# ManniRaspiRadio.net
KiCad netlist of a schematic drawn in EAGLE
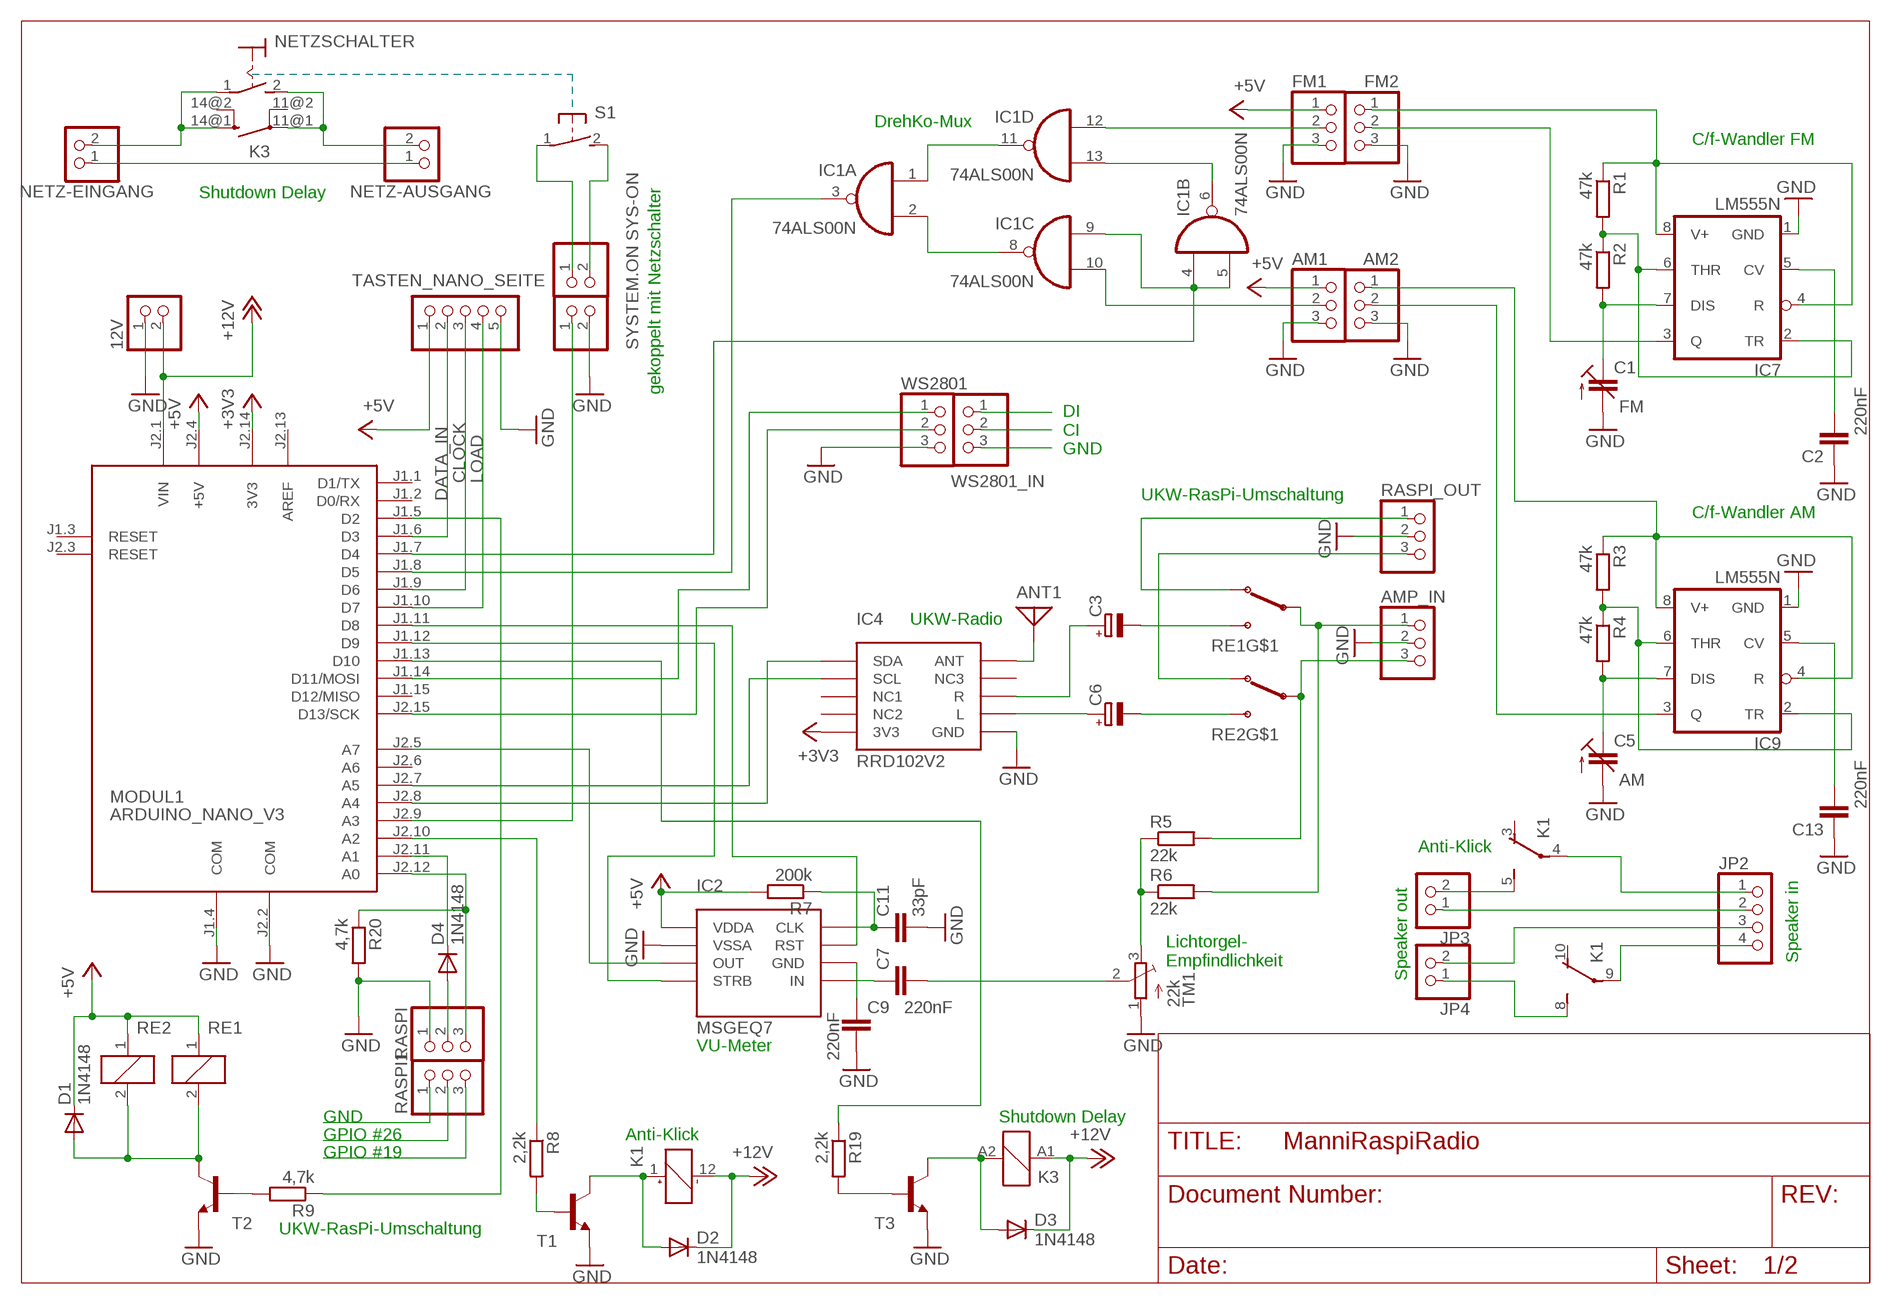
[diagram p0: schematic, sheet 1]
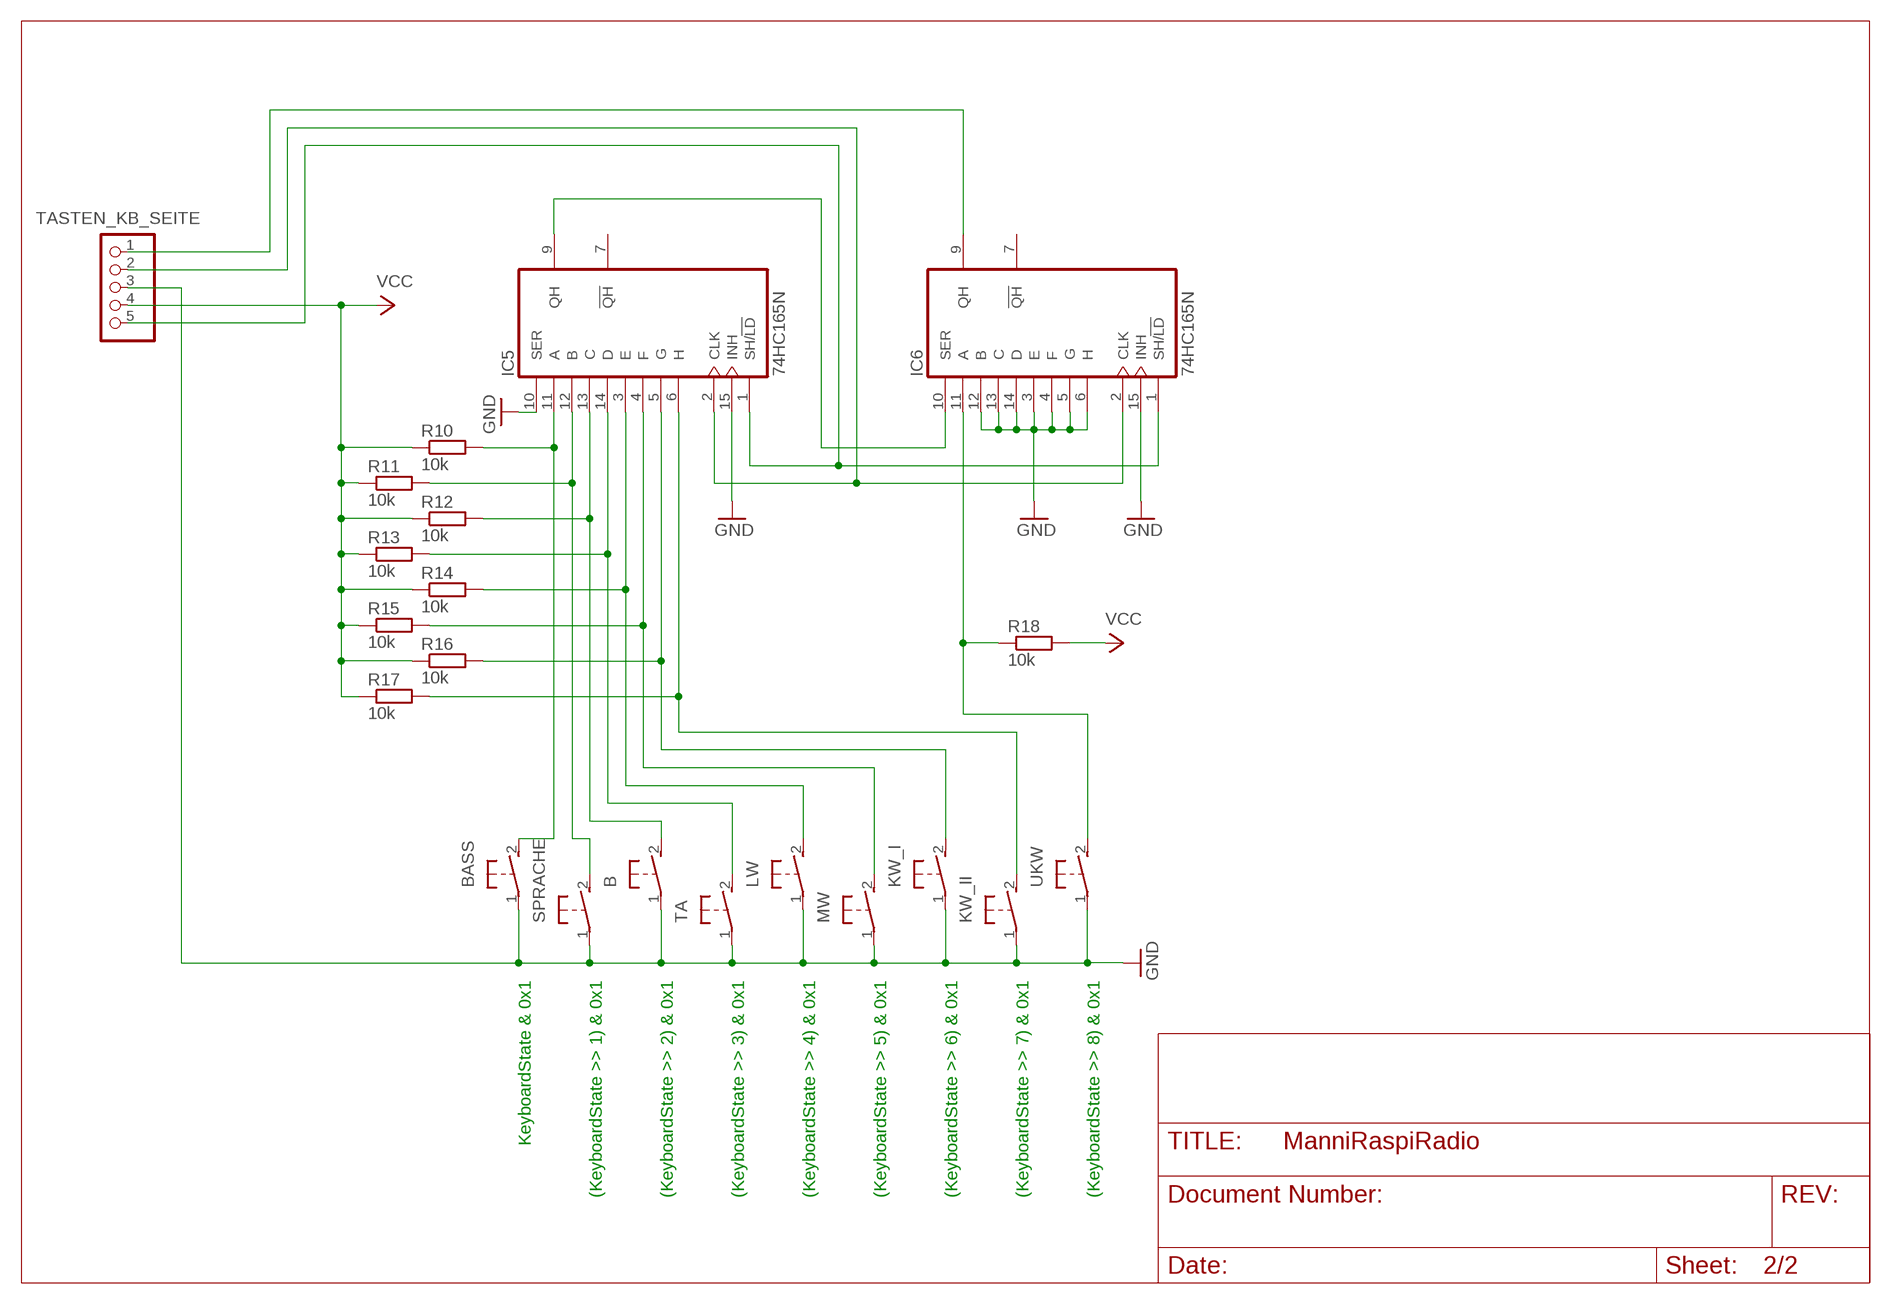
[diagram p1: schematic, sheet 2]

(export (version "E")
  (design (tool "Eeschema 10.0.6"))
  (components
    (comp (ref "12V")
      (value "PINHD-1X2")
      (footprint "eagle-import:1X02")
      (libsource (lib "eagle-import") (part "PINHD-1X2"))
    )
    (comp (ref "AM1")
      (value "PINHD-1X3")
      (footprint "eagle-import:1X03")
      (libsource (lib "eagle-import") (part "PINHD-1X3"))
    )
    (comp (ref "AM2")
      (value "PINHD-1X3")
      (footprint "eagle-import:1X03")
      (libsource (lib "eagle-import") (part "PINHD-1X3"))
    )
    (comp (ref "AMP_IN")
      (value "PINHD-1X3")
      (footprint "eagle-import:1X03")
      (libsource (lib "eagle-import") (part "PINHD-1X3"))
    )
    (comp (ref "ANT1")
      (value "ANTENNA")
      (footprint "eagle-import:PAD-01")
      (libsource (lib "eagle-import") (part "ANTENNA"))
    )
    (comp (ref "C1")
      (value "FM")
      (footprint "eagle-import:CTRIM3018_12")
      (libsource (lib "eagle-import") (part "C-TRIMM3018_12"))
    )
    (comp (ref "C2")
      (value "220nF")
      (footprint "eagle-import:C025-030X050")
      (libsource (lib "eagle-import") (part "C-EU025-030X050"))
    )
    (comp (ref "C3")
      (value "CPOL-EU139CLL-2W")
      (footprint "eagle-import:139CLL-2W")
      (libsource (lib "eagle-import") (part "CPOL-EU139CLL-2W"))
    )
    (comp (ref "C5")
      (value "AM")
      (footprint "eagle-import:CTRIM3018_12")
      (libsource (lib "eagle-import") (part "C-TRIMM3018_12"))
    )
    (comp (ref "C6")
      (value "CPOL-EU139CLL-2W")
      (footprint "eagle-import:139CLL-2W")
      (libsource (lib "eagle-import") (part "CPOL-EU139CLL-2W"))
    )
    (comp (ref "C7")
      (value "220nF")
      (footprint "eagle-import:C025-030X050")
      (libsource (lib "eagle-import") (part "C-EU025-030X050"))
    )
    (comp (ref "C9")
      (value "220nF")
      (footprint "eagle-import:C025-030X050")
      (libsource (lib "eagle-import") (part "C-EU025-030X050"))
    )
    (comp (ref "C11")
      (value "33pF")
      (footprint "eagle-import:C025-030X050")
      (libsource (lib "eagle-import") (part "C-EU025-030X050"))
    )
    (comp (ref "C13")
      (value "220nF")
      (footprint "eagle-import:C025-030X050")
      (libsource (lib "eagle-import") (part "C-EU025-030X050"))
    )
    (comp (ref "D1")
      (value "1N4148")
      (footprint "eagle-import:DO35-10")
      (libsource (lib "eagle-import") (part "1N4148DO35-10"))
    )
    (comp (ref "D2")
      (value "1N4148")
      (footprint "eagle-import:DO35-10")
      (libsource (lib "eagle-import") (part "1N4148DO35-10"))
    )
    (comp (ref "D3")
      (value "1N4148")
      (footprint "eagle-import:DO35-10")
      (libsource (lib "eagle-import") (part "1N4148DO35-10"))
    )
    (comp (ref "D4")
      (value "1N4148")
      (footprint "eagle-import:DO35-10")
      (libsource (lib "eagle-import") (part "1N4148DO35-10"))
    )
    (comp (ref "FM1")
      (value "PINHD-1X3")
      (footprint "eagle-import:1X03")
      (libsource (lib "eagle-import") (part "PINHD-1X3"))
    )
    (comp (ref "FM2")
      (value "PINHD-1X3")
      (footprint "eagle-import:1X03")
      (libsource (lib "eagle-import") (part "PINHD-1X3"))
    )
    (comp (ref "IC1")
      (value "74ALS00N")
      (footprint "eagle-import:DIL14")
      (libsource (lib "eagle-import") (part "7400NALS"))
    )
    (comp (ref "IC2")
      (value "MSGEQ7")
      (footprint "eagle-import:MSGEQ7")
      (libsource (lib "eagle-import") (part "MSGEQ7"))
    )
    (comp (ref "IC4")
      (value "RRD102V2")
      (footprint "eagle-import:RRD102V2")
      (libsource (lib "eagle-import") (part "RRD102V2"))
    )
    (comp (ref "IC7")
      (value "LM555N")
      (footprint "eagle-import:DIL08")
      (libsource (lib "eagle-import") (part "555NLM"))
    )
    (comp (ref "IC9")
      (value "LM555N")
      (footprint "eagle-import:DIL08")
      (libsource (lib "eagle-import") (part "555NLM"))
    )
    (comp (ref "JP2")
      (value "PINHD-1X4")
      (footprint "eagle-import:1X04")
      (libsource (lib "eagle-import") (part "PINHD-1X4"))
    )
    (comp (ref "JP3")
      (value "PINHD-1X2")
      (footprint "eagle-import:1X02")
      (libsource (lib "eagle-import") (part "PINHD-1X2"))
    )
    (comp (ref "JP4")
      (value "PINHD-1X2")
      (footprint "eagle-import:1X02")
      (libsource (lib "eagle-import") (part "PINHD-1X2"))
    )
    (comp (ref "K1")
      (value "TXD2-12V")
      (footprint "eagle-import:TXD2")
      (libsource (lib "eagle-import") (part "TX?-D212V"))
    )
    (comp (ref "K3")
      (value "FINDER-43.61")
      (footprint "eagle-import:FINDER-43.61")
      (libsource (lib "eagle-import") (part "FINDER-43.61"))
    )
    (comp (ref "MODUL1")
      (value "ARDUINO_NANO_V3")
      (footprint "eagle-import:ARDUINO_NANO2")
      (libsource (lib "eagle-import") (part "ARDUINO_NANO2"))
    )
    (comp (ref "NETZ-AUSGANG")
      (value "PINHD-1X2")
      (footprint "eagle-import:1X02")
      (libsource (lib "eagle-import") (part "PINHD-1X2"))
    )
    (comp (ref "NETZ-EINGANG")
      (value "PINHD-1X2")
      (footprint "eagle-import:1X02")
      (libsource (lib "eagle-import") (part "PINHD-1X2"))
    )
    (comp (ref "NETZSCHALTER")
      (value "MS243")
      (footprint "eagle-import:MS243")
      (libsource (lib "eagle-import") (part "MS243"))
    )
    (comp (ref "R1")
      (value "47k")
      (footprint "eagle-import:0207_10")
      (libsource (lib "eagle-import") (part "R-EU_0207/10"))
    )
    (comp (ref "R2")
      (value "47k")
      (footprint "eagle-import:0207_10")
      (libsource (lib "eagle-import") (part "R-EU_0207/10"))
    )
    (comp (ref "R3")
      (value "47k")
      (footprint "eagle-import:0207_10")
      (libsource (lib "eagle-import") (part "R-EU_0207/10"))
    )
    (comp (ref "R4")
      (value "47k")
      (footprint "eagle-import:0207_10")
      (libsource (lib "eagle-import") (part "R-EU_0207/10"))
    )
    (comp (ref "R5")
      (value "22k")
      (footprint "eagle-import:0207_10")
      (libsource (lib "eagle-import") (part "R-EU_0207/10"))
    )
    (comp (ref "R6")
      (value "22k")
      (footprint "eagle-import:0207_10")
      (libsource (lib "eagle-import") (part "R-EU_0207/10"))
    )
    (comp (ref "R7")
      (value "200k")
      (footprint "eagle-import:0207_10")
      (libsource (lib "eagle-import") (part "R-EU_0207/10"))
    )
    (comp (ref "R8")
      (value "2,2k")
      (footprint "eagle-import:0207_10")
      (libsource (lib "eagle-import") (part "R-EU_0207/10"))
    )
    (comp (ref "R9")
      (value "4,7k")
      (footprint "eagle-import:0207_10")
      (libsource (lib "eagle-import") (part "R-EU_0207/10"))
    )
    (comp (ref "R19")
      (value "2,2k")
      (footprint "eagle-import:0207_10")
      (libsource (lib "eagle-import") (part "R-EU_0207/10"))
    )
    (comp (ref "R20")
      (value "4,7k")
      (footprint "eagle-import:0207_10")
      (libsource (lib "eagle-import") (part "R-EU_0207/10"))
    )
    (comp (ref "RASPI")
      (value "PINHD-1X3")
      (footprint "eagle-import:1X03")
      (libsource (lib "eagle-import") (part "PINHD-1X3"))
    )
    (comp (ref "RASPI1")
      (value "PINHD-1X3")
      (footprint "eagle-import:1X03")
      (libsource (lib "eagle-import") (part "PINHD-1X3"))
    )
    (comp (ref "RASPI_OUT")
      (value "PINHD-1X3")
      (footprint "eagle-import:1X03")
      (libsource (lib "eagle-import") (part "PINHD-1X3"))
    )
    (comp (ref "RE1")
      (value "RE-SPDT--G5LE")
      (footprint "eagle-import:EPP-RELAY-G5LE")
      (libsource (lib "eagle-import") (part "RE-SPDT--G5LE"))
    )
    (comp (ref "RE2")
      (value "RE-SPDT--G5LE")
      (footprint "eagle-import:EPP-RELAY-G5LE")
      (libsource (lib "eagle-import") (part "RE-SPDT--G5LE"))
    )
    (comp (ref "S1")
      (value "31-XX")
      (footprint "eagle-import:B3F-31XX")
      (libsource (lib "eagle-import") (part "31-XX"))
    )
    (comp (ref "SYS-ON")
      (value "PINHD-1X2")
      (footprint "eagle-import:1X02")
      (libsource (lib "eagle-import") (part "PINHD-1X2"))
    )
    (comp (ref "SYSTEM.ON")
      (value "PINHD-1X2")
      (footprint "eagle-import:1X02")
      (libsource (lib "eagle-import") (part "PINHD-1X2"))
    )
    (comp (ref "T1")
      (value "T-NPN-BC337-")
      (footprint "eagle-import:EPP-TO-92")
      (libsource (lib "eagle-import") (part "T-NPN--BC337"))
    )
    (comp (ref "T2")
      (value "T-NPN-BC337-")
      (footprint "eagle-import:EPP-TO-92")
      (libsource (lib "eagle-import") (part "T-NPN--BC337"))
    )
    (comp (ref "T3")
      (value "T-NPN-BC337-")
      (footprint "eagle-import:EPP-TO-92")
      (libsource (lib "eagle-import") (part "T-NPN--BC337"))
    )
    (comp (ref "TASTEN_NANO_SEITE")
      (value "PINHD-1X5")
      (footprint "eagle-import:1X05")
      (libsource (lib "eagle-import") (part "PINHD-1X5"))
    )
    (comp (ref "TM1")
      (value "22k")
      (footprint "eagle-import:TRIM-3386")
      (libsource (lib "eagle-import") (part "TRIMPOT3386"))
    )
    (comp (ref "WS2801")
      (value "PINHD-1X3")
      (footprint "eagle-import:1X03")
      (libsource (lib "eagle-import") (part "PINHD-1X3"))
    )
    (comp (ref "WS2801_IN")
      (value "PINHD-1X3")
      (footprint "eagle-import:1X03")
      (libsource (lib "eagle-import") (part "PINHD-1X3"))
    )
    (comp (ref "B")
      (value "31-XX")
      (footprint "eagle-import:B3F-31XX")
      (libsource (lib "eagle-import") (part "31-XX"))
    )
    (comp (ref "BASS")
      (value "31-XX")
      (footprint "eagle-import:B3F-31XX")
      (libsource (lib "eagle-import") (part "31-XX"))
    )
    (comp (ref "IC5")
      (value "74HC165N")
      (footprint "eagle-import:DIL16")
      (libsource (lib "eagle-import") (part "74165NHC"))
    )
    (comp (ref "IC6")
      (value "74HC165N")
      (footprint "eagle-import:DIL16")
      (libsource (lib "eagle-import") (part "74165NHC"))
    )
    (comp (ref "KW_I")
      (value "31-XX")
      (footprint "eagle-import:B3F-31XX")
      (libsource (lib "eagle-import") (part "31-XX"))
    )
    (comp (ref "KW_II")
      (value "31-XX")
      (footprint "eagle-import:B3F-31XX")
      (libsource (lib "eagle-import") (part "31-XX"))
    )
    (comp (ref "LW")
      (value "31-XX")
      (footprint "eagle-import:B3F-31XX")
      (libsource (lib "eagle-import") (part "31-XX"))
    )
    (comp (ref "MW")
      (value "31-XX")
      (footprint "eagle-import:B3F-31XX")
      (libsource (lib "eagle-import") (part "31-XX"))
    )
    (comp (ref "R10")
      (value "10k")
      (footprint "eagle-import:0207_10")
      (libsource (lib "eagle-import") (part "R-EU_0207/10"))
    )
    (comp (ref "R11")
      (value "10k")
      (footprint "eagle-import:0207_10")
      (libsource (lib "eagle-import") (part "R-EU_0207/10"))
    )
    (comp (ref "R12")
      (value "10k")
      (footprint "eagle-import:0207_10")
      (libsource (lib "eagle-import") (part "R-EU_0207/10"))
    )
    (comp (ref "R13")
      (value "10k")
      (footprint "eagle-import:0207_10")
      (libsource (lib "eagle-import") (part "R-EU_0207/10"))
    )
    (comp (ref "R14")
      (value "10k")
      (footprint "eagle-import:0207_10")
      (libsource (lib "eagle-import") (part "R-EU_0207/10"))
    )
    (comp (ref "R15")
      (value "10k")
      (footprint "eagle-import:0207_10")
      (libsource (lib "eagle-import") (part "R-EU_0207/10"))
    )
    (comp (ref "R16")
      (value "10k")
      (footprint "eagle-import:0207_10")
      (libsource (lib "eagle-import") (part "R-EU_0207/10"))
    )
    (comp (ref "R17")
      (value "10k")
      (footprint "eagle-import:0207_10")
      (libsource (lib "eagle-import") (part "R-EU_0207/10"))
    )
    (comp (ref "R18")
      (value "10k")
      (footprint "eagle-import:0207_10")
      (libsource (lib "eagle-import") (part "R-EU_0207/10"))
    )
    (comp (ref "SPRACHE")
      (value "31-XX")
      (footprint "eagle-import:B3F-31XX")
      (libsource (lib "eagle-import") (part "31-XX"))
    )
    (comp (ref "TA")
      (value "31-XX")
      (footprint "eagle-import:B3F-31XX")
      (libsource (lib "eagle-import") (part "31-XX"))
    )
    (comp (ref "TASTEN_KB_SEITE")
      (value "PINHD-1X5")
      (footprint "eagle-import:1X05")
      (libsource (lib "eagle-import") (part "PINHD-1X5"))
    )
    (comp (ref "UKW")
      (value "31-XX")
      (footprint "eagle-import:B3F-31XX")
      (libsource (lib "eagle-import") (part "31-XX"))
    )
  )
  (nets
    (net (code "1") (name "+3V3") (class "Default")
      (node (ref "IC4") (pin "P$5") (pinfunction "3V3_P$5") (pintype "power_in"))
      (node (ref "MODUL1") (pin "J2.14") (pinfunction "3V3_J2.14") (pintype "power_in"))
    )
    (net (code "2") (name "+5V") (class "Default")
      (node (ref "AM1") (pin "1") (pinfunction "1_1") (pintype "passive"))
      (node (ref "D1") (pin "C") (pinfunction "C_C") (pintype "passive"))
      (node (ref "FM1") (pin "1") (pinfunction "1_1") (pintype "passive"))
      (node (ref "IC2") (pin "P$1") (pinfunction "VDDA_P$1") (pintype "power_in"))
      (node (ref "MODUL1") (pin "J2.4") (pinfunction "+5V_J2.4") (pintype "power_in"))
      (node (ref "R7") (pin "2") (pinfunction "2_2") (pintype "passive"))
      (node (ref "RE1") (pin "1") (pinfunction "1_1") (pintype "passive"))
      (node (ref "RE2") (pin "1") (pinfunction "1_1") (pintype "passive"))
      (node (ref "TASTEN_NANO_SEITE") (pin "1") (pinfunction "1_1") (pintype "passive"))
    )
    (net (code "3") (name "+12V") (class "Default")
      (node (ref "12V") (pin "2") (pinfunction "2_2") (pintype "passive"))
      (node (ref "D2") (pin "C") (pinfunction "C_C") (pintype "passive"))
      (node (ref "D3") (pin "C") (pinfunction "C_C") (pintype "passive"))
      (node (ref "K1") (pin "12") (pinfunction "-_12") (pintype "passive"))
      (node (ref "K3") (pin "A1") (pinfunction "1_A1") (pintype "passive"))
      (node (ref "MODUL1") (pin "J2.1") (pinfunction "VIN_J2.1") (pintype "power_in"))
    )
    (net (code "4") (name "AREF") (class "Default")
      (node (ref "MODUL1") (pin "J2.13") (pinfunction "AREF_J2.13") (pintype "power_in"))
    )
    (net (code "5") (name "CLOCK") (class "Default")
      (node (ref "MODUL1") (pin "J1.9") (pinfunction "D6_J1.9") (pintype "bidirectional"))
      (node (ref "TASTEN_NANO_SEITE") (pin "3") (pinfunction "3_3") (pintype "passive"))
    )
    (net (code "6") (name "DATA_IN") (class "Default")
      (node (ref "MODUL1") (pin "J1.6") (pinfunction "D3_J1.6") (pintype "bidirectional"))
      (node (ref "TASTEN_NANO_SEITE") (pin "2") (pinfunction "2_2") (pintype "passive"))
    )
    (net (code "7") (name "GND") (class "Default")
      (node (ref "12V") (pin "1") (pinfunction "1_1") (pintype "passive"))
      (node (ref "AM1") (pin "3") (pinfunction "3_3") (pintype "passive"))
      (node (ref "AM2") (pin "3") (pinfunction "3_3") (pintype "passive"))
      (node (ref "AMP_IN") (pin "2") (pinfunction "2_2") (pintype "passive"))
      (node (ref "B") (pin "1") (pinfunction "P_1") (pintype "passive"))
      (node (ref "BASS") (pin "1") (pinfunction "P_1") (pintype "passive"))
      (node (ref "C1") (pin "-") (pinfunction "A_-") (pintype "passive"))
      (node (ref "C11") (pin "2") (pinfunction "2_2") (pintype "passive"))
      (node (ref "C13") (pin "1") (pinfunction "1_1") (pintype "passive"))
      (node (ref "C2") (pin "1") (pinfunction "1_1") (pintype "passive"))
      (node (ref "C5") (pin "-") (pinfunction "A_-") (pintype "passive"))
      (node (ref "C9") (pin "2") (pinfunction "2_2") (pintype "passive"))
      (node (ref "FM1") (pin "3") (pinfunction "3_3") (pintype "passive"))
      (node (ref "FM2") (pin "3") (pinfunction "3_3") (pintype "passive"))
      (node (ref "IC2") (pin "P$2") (pinfunction "VSSA_P$2") (pintype "power_in"))
      (node (ref "IC4") (pin "P$6") (pinfunction "GND_P$6") (pintype "bidirectional"))
      (node (ref "IC5") (pin "10") (pinfunction "SER_10") (pintype "input"))
      (node (ref "IC5") (pin "15") (pinfunction "INH_15") (pintype "input"))
      (node (ref "IC6") (pin "12") (pinfunction "B_12") (pintype "input"))
      (node (ref "IC6") (pin "13") (pinfunction "C_13") (pintype "input"))
      (node (ref "IC6") (pin "14") (pinfunction "D_14") (pintype "input"))
      (node (ref "IC6") (pin "15") (pinfunction "INH_15") (pintype "input"))
      (node (ref "IC6") (pin "3") (pinfunction "E_3") (pintype "input"))
      (node (ref "IC6") (pin "4") (pinfunction "F_4") (pintype "input"))
      (node (ref "IC6") (pin "5") (pinfunction "G_5") (pintype "input"))
      (node (ref "IC6") (pin "6") (pinfunction "H_6") (pintype "input"))
      (node (ref "IC7") (pin "1") (pinfunction "GND_1") (pintype "power_in"))
      (node (ref "IC9") (pin "1") (pinfunction "GND_1") (pintype "power_in"))
      (node (ref "KW_I") (pin "1") (pinfunction "P_1") (pintype "passive"))
      (node (ref "KW_II") (pin "1") (pinfunction "P_1") (pintype "passive"))
      (node (ref "LW") (pin "1") (pinfunction "P_1") (pintype "passive"))
      (node (ref "MODUL1") (pin "J1.4") (pinfunction "COM_J1.4") (pintype "power_in"))
      (node (ref "MODUL1") (pin "J2.2") (pinfunction "COM_J2.2") (pintype "power_in"))
      (node (ref "MW") (pin "1") (pinfunction "P_1") (pintype "passive"))
      (node (ref "R20") (pin "2") (pinfunction "2_2") (pintype "passive"))
      (node (ref "RASPI") (pin "1") (pinfunction "1_1") (pintype "passive"))
      (node (ref "RASPI_OUT") (pin "2") (pinfunction "2_2") (pintype "passive"))
      (node (ref "SPRACHE") (pin "1") (pinfunction "P_1") (pintype "passive"))
      (node (ref "SYSTEM.ON") (pin "2") (pinfunction "2_2") (pintype "passive"))
      (node (ref "T1") (pin "3") (pinfunction "E_3") (pintype "passive"))
      (node (ref "T2") (pin "3") (pinfunction "E_3") (pintype "passive"))
      (node (ref "T3") (pin "3") (pinfunction "E_3") (pintype "passive"))
      (node (ref "TA") (pin "1") (pinfunction "P_1") (pintype "passive"))
      (node (ref "TASTEN_KB_SEITE") (pin "3") (pinfunction "3_3") (pintype "passive"))
      (node (ref "TASTEN_NANO_SEITE") (pin "5") (pinfunction "5_5") (pintype "passive"))
      (node (ref "TM1") (pin "1") (pinfunction "A_1") (pintype "passive"))
      (node (ref "UKW") (pin "1") (pinfunction "P_1") (pintype "passive"))
      (node (ref "WS2801") (pin "3") (pinfunction "3_3") (pintype "passive"))
    )
    (net (code "8") (name "LOAD") (class "Default")
      (node (ref "MODUL1") (pin "J1.10") (pinfunction "D7_J1.10") (pintype "bidirectional"))
      (node (ref "TASTEN_NANO_SEITE") (pin "4") (pinfunction "4_4") (pintype "passive"))
    )
    (net (code "9") (name "Net-(AMP_IN-Pad1)") (class "Default")
      (node (ref "AMP_IN") (pin "1") (pinfunction "1_1") (pintype "passive"))
      (node (ref "R6") (pin "2") (pinfunction "2_2") (pintype "passive"))
      (node (ref "RE1") (pin "P") (pinfunction "P_P") (pintype "passive"))
    )
    (net (code "10") (name "Net-(AMP_IN-Pad3)") (class "Default")
      (node (ref "AMP_IN") (pin "3") (pinfunction "3_3") (pintype "passive"))
      (node (ref "R5") (pin "2") (pinfunction "2_2") (pintype "passive"))
      (node (ref "RE2") (pin "P") (pinfunction "P_P") (pintype "passive"))
    )
    (net (code "11") (name "Net-(B-S)") (class "Default")
      (node (ref "B") (pin "2") (pinfunction "S_2") (pintype "passive"))
      (node (ref "IC5") (pin "13") (pinfunction "C_13") (pintype "input"))
      (node (ref "R12") (pin "2") (pinfunction "2_2") (pintype "passive"))
    )
    (net (code "12") (name "Net-(BASS-S)") (class "Default")
      (node (ref "BASS") (pin "2") (pinfunction "S_2") (pintype "passive"))
      (node (ref "IC5") (pin "11") (pinfunction "A_11") (pintype "input"))
      (node (ref "R10") (pin "2") (pinfunction "2_2") (pintype "passive"))
    )
    (net (code "13") (name "Net-(C1-E)") (class "Default")
      (node (ref "C1") (pin "+") (pinfunction "E_+") (pintype "passive"))
      (node (ref "IC7") (pin "7") (pinfunction "DIS_7") (pintype "input"))
      (node (ref "R2") (pin "2") (pinfunction "2_2") (pintype "passive"))
    )
    (net (code "14") (name "Net-(C3-Pad-)") (class "Default")
      (node (ref "C3") (pin "-") (pinfunction "-_-") (pintype "passive"))
      (node (ref "RE1") (pin "S") (pinfunction "S_S") (pintype "passive"))
    )
    (net (code "15") (name "Net-(C5-E)") (class "Default")
      (node (ref "C5") (pin "+") (pinfunction "E_+") (pintype "passive"))
      (node (ref "IC9") (pin "7") (pinfunction "DIS_7") (pintype "input"))
      (node (ref "R4") (pin "2") (pinfunction "2_2") (pintype "passive"))
    )
    (net (code "16") (name "Net-(C6-Pad-)") (class "Default")
      (node (ref "C6") (pin "-") (pinfunction "-_-") (pintype "passive"))
      (node (ref "RE2") (pin "S") (pinfunction "S_S") (pintype "passive"))
    )
    (net (code "17") (name "Net-(D4-PadA)") (class "Default")
      (node (ref "D4") (pin "A") (pinfunction "A_A") (pintype "passive"))
      (node (ref "RASPI") (pin "2") (pinfunction "2_2") (pintype "passive"))
    )
    (net (code "18") (name "Net-(IC1A-I0)") (class "Default")
      (node (ref "IC1") (pin "1") (pinfunction "I0_1") (pintype "input"))
      (node (ref "IC1") (pin "11") (pinfunction "O_11") (pintype "output"))
    )
    (net (code "19") (name "Net-(IC1A-I1)") (class "Default")
      (node (ref "IC1") (pin "2") (pinfunction "I1_2") (pintype "input"))
      (node (ref "IC1") (pin "8") (pinfunction "O_8") (pintype "output"))
    )
    (net (code "20") (name "Net-(IC1A-O)") (class "Default")
      (node (ref "IC1") (pin "3") (pinfunction "O_3") (pintype "output"))
      (node (ref "MODUL1") (pin "J1.8") (pinfunction "D5_J1.8") (pintype "bidirectional"))
    )
    (net (code "21") (name "Net-(IC1B-I0)") (class "Default")
      (node (ref "IC1") (pin "4") (pinfunction "I0_4") (pintype "input"))
      (node (ref "IC1") (pin "5") (pinfunction "I1_5") (pintype "input"))
      (node (ref "IC1") (pin "9") (pinfunction "I0_9") (pintype "input"))
      (node (ref "MODUL1") (pin "J1.7") (pinfunction "D4_J1.7") (pintype "bidirectional"))
    )
    (net (code "22") (name "Net-(IC1B-O)") (class "Default")
      (node (ref "IC1") (pin "13") (pinfunction "I1_13") (pintype "input"))
      (node (ref "IC1") (pin "6") (pinfunction "O_6") (pintype "output"))
    )
    (net (code "23") (name "Net-(IC1C-I1)") (class "Default")
      (node (ref "AM1") (pin "2") (pinfunction "2_2") (pintype "passive"))
      (node (ref "IC1") (pin "10") (pinfunction "I1_10") (pintype "input"))
    )
    (net (code "24") (name "Net-(IC1D-I0)") (class "Default")
      (node (ref "FM1") (pin "2") (pinfunction "2_2") (pintype "passive"))
      (node (ref "IC1") (pin "12") (pinfunction "I0_12") (pintype "input"))
    )
    (net (code "25") (name "Net-(IC2-CLK)") (class "Default")
      (node (ref "C11") (pin "1") (pinfunction "1_1") (pintype "passive"))
      (node (ref "IC2") (pin "P$8") (pinfunction "CLK_P$8") (pintype "bidirectional"))
      (node (ref "R7") (pin "1") (pinfunction "1_1") (pintype "passive"))
    )
    (net (code "26") (name "Net-(IC2-GND)") (class "Default")
      (node (ref "C9") (pin "1") (pinfunction "1_1") (pintype "passive"))
      (node (ref "IC2") (pin "P$6") (pinfunction "GND_P$6") (pintype "power_in"))
    )
    (net (code "27") (name "Net-(IC2-IN)") (class "Default")
      (node (ref "C7") (pin "1") (pinfunction "1_1") (pintype "passive"))
      (node (ref "IC2") (pin "P$5") (pinfunction "IN_P$5") (pintype "input"))
    )
    (net (code "28") (name "Net-(IC2-OUT)") (class "Default")
      (node (ref "IC2") (pin "P$3") (pinfunction "OUT_P$3") (pintype "output"))
      (node (ref "MODUL1") (pin "J2.5") (pinfunction "A7_J2.5") (pintype "bidirectional"))
    )
    (net (code "29") (name "Net-(IC2-RST)") (class "Default")
      (node (ref "IC2") (pin "P$7") (pinfunction "RST_P$7") (pintype "input"))
      (node (ref "MODUL1") (pin "J1.11") (pinfunction "D8_J1.11") (pintype "bidirectional"))
    )
    (net (code "30") (name "Net-(IC2-STRB)") (class "Default")
      (node (ref "IC2") (pin "P$4") (pinfunction "STRB_P$4") (pintype "input"))
      (node (ref "MODUL1") (pin "J1.12") (pinfunction "D9_J1.12") (pintype "bidirectional"))
    )
    (net (code "31") (name "Net-(IC4-ANT)") (class "Default")
      (node (ref "ANT1") (pin "1") (pinfunction "1_1") (pintype "output"))
      (node (ref "IC4") (pin "P$10") (pinfunction "ANT_P$10") (pintype "input"))
    )
    (net (code "32") (name "Net-(IC4-L)") (class "Default")
      (node (ref "C6") (pin "+") (pinfunction "+_+") (pintype "passive"))
      (node (ref "IC4") (pin "P$7") (pinfunction "L_P$7") (pintype "output"))
    )
    (net (code "33") (name "Net-(IC4-R)") (class "Default")
      (node (ref "C3") (pin "+") (pinfunction "+_+") (pintype "passive"))
      (node (ref "IC4") (pin "P$8") (pinfunction "R_P$8") (pintype "output"))
    )
    (net (code "34") (name "Net-(IC4-SCL)") (class "Default")
      (node (ref "IC4") (pin "P$2") (pinfunction "SCL_P$2") (pintype "bidirectional"))
      (node (ref "MODUL1") (pin "J2.7") (pinfunction "A5_J2.7") (pintype "bidirectional"))
    )
    (net (code "35") (name "Net-(IC4-SDA)") (class "Default")
      (node (ref "IC4") (pin "P$1") (pinfunction "SDA_P$1") (pintype "bidirectional"))
      (node (ref "MODUL1") (pin "J2.8") (pinfunction "A4_J2.8") (pintype "bidirectional"))
    )
    (net (code "36") (name "Net-(IC5A-B)") (class "Default")
      (node (ref "IC5") (pin "12") (pinfunction "B_12") (pintype "input"))
      (node (ref "R11") (pin "2") (pinfunction "2_2") (pintype "passive"))
      (node (ref "SPRACHE") (pin "2") (pinfunction "S_2") (pintype "passive"))
    )
    (net (code "37") (name "Net-(IC5A-CLK)") (class "Default")
      (node (ref "IC5") (pin "2") (pinfunction "CLK_2") (pintype "input"))
      (node (ref "IC6") (pin "2") (pinfunction "CLK_2") (pintype "input"))
      (node (ref "TASTEN_KB_SEITE") (pin "2") (pinfunction "2_2") (pintype "passive"))
    )
    (net (code "38") (name "Net-(IC5A-D)") (class "Default")
      (node (ref "IC5") (pin "14") (pinfunction "D_14") (pintype "input"))
      (node (ref "R13") (pin "2") (pinfunction "2_2") (pintype "passive"))
      (node (ref "TA") (pin "2") (pinfunction "S_2") (pintype "passive"))
    )
    (net (code "39") (name "Net-(IC5A-E)") (class "Default")
      (node (ref "IC5") (pin "3") (pinfunction "E_3") (pintype "input"))
      (node (ref "LW") (pin "2") (pinfunction "S_2") (pintype "passive"))
      (node (ref "R14") (pin "2") (pinfunction "2_2") (pintype "passive"))
    )
    (net (code "40") (name "Net-(IC5A-F)") (class "Default")
      (node (ref "IC5") (pin "4") (pinfunction "F_4") (pintype "input"))
      (node (ref "MW") (pin "2") (pinfunction "S_2") (pintype "passive"))
      (node (ref "R15") (pin "2") (pinfunction "2_2") (pintype "passive"))
    )
    (net (code "41") (name "Net-(IC5A-G)") (class "Default")
      (node (ref "IC5") (pin "5") (pinfunction "G_5") (pintype "input"))
      (node (ref "KW_I") (pin "2") (pinfunction "S_2") (pintype "passive"))
      (node (ref "R16") (pin "2") (pinfunction "2_2") (pintype "passive"))
    )
    (net (code "42") (name "Net-(IC5A-H)") (class "Default")
      (node (ref "IC5") (pin "6") (pinfunction "H_6") (pintype "input"))
      (node (ref "KW_II") (pin "2") (pinfunction "S_2") (pintype "passive"))
      (node (ref "R17") (pin "2") (pinfunction "2_2") (pintype "passive"))
    )
    (net (code "43") (name "Net-(IC5A-QH)") (class "Default")
      (node (ref "IC5") (pin "9") (pinfunction "QH_9") (pintype "output"))
      (node (ref "IC6") (pin "10") (pinfunction "SER_10") (pintype "input"))
    )
    (net (code "44") (name "Net-(IC5A-SH{slash}~{LD})") (class "Default")
      (node (ref "IC5") (pin "1") (pinfunction "SH/~{LD}_1") (pintype "input"))
      (node (ref "IC6") (pin "1") (pinfunction "SH/~{LD}_1") (pintype "input"))
      (node (ref "TASTEN_KB_SEITE") (pin "5") (pinfunction "5_5") (pintype "passive"))
    )
    (net (code "45") (name "Net-(IC6A-A)") (class "Default")
      (node (ref "IC6") (pin "11") (pinfunction "A_11") (pintype "input"))
      (node (ref "R18") (pin "1") (pinfunction "1_1") (pintype "passive"))
      (node (ref "UKW") (pin "2") (pinfunction "S_2") (pintype "passive"))
    )
    (net (code "46") (name "Net-(IC6A-QH)") (class "Default")
      (node (ref "IC6") (pin "9") (pinfunction "QH_9") (pintype "output"))
      (node (ref "TASTEN_KB_SEITE") (pin "1") (pinfunction "1_1") (pintype "passive"))
    )
    (net (code "47") (name "Net-(IC7-CV)") (class "Default")
      (node (ref "C2") (pin "2") (pinfunction "2_2") (pintype "passive"))
      (node (ref "IC7") (pin "5") (pinfunction "CV_5") (pintype "input"))
    )
    (net (code "48") (name "Net-(IC7-Q)") (class "Default")
      (node (ref "FM2") (pin "2") (pinfunction "2_2") (pintype "passive"))
      (node (ref "IC7") (pin "3") (pinfunction "Q_3") (pintype "output"))
    )
    (net (code "49") (name "Net-(IC7-R)") (class "Default")
      (node (ref "FM2") (pin "1") (pinfunction "1_1") (pintype "passive"))
      (node (ref "IC7") (pin "4") (pinfunction "R_4") (pintype "input"))
      (node (ref "IC7") (pin "8") (pinfunction "V+_8") (pintype "power_in"))
      (node (ref "R1") (pin "1") (pinfunction "1_1") (pintype "passive"))
    )
    (net (code "50") (name "Net-(IC7-THR)") (class "Default")
      (node (ref "IC7") (pin "2") (pinfunction "TR_2") (pintype "input"))
      (node (ref "IC7") (pin "6") (pinfunction "THR_6") (pintype "input"))
      (node (ref "R1") (pin "2") (pinfunction "2_2") (pintype "passive"))
      (node (ref "R2") (pin "1") (pinfunction "1_1") (pintype "passive"))
    )
    (net (code "51") (name "Net-(IC9-CV)") (class "Default")
      (node (ref "C13") (pin "2") (pinfunction "2_2") (pintype "passive"))
      (node (ref "IC9") (pin "5") (pinfunction "CV_5") (pintype "input"))
    )
    (net (code "52") (name "Net-(IC9-Q)") (class "Default")
      (node (ref "AM2") (pin "2") (pinfunction "2_2") (pintype "passive"))
      (node (ref "IC9") (pin "3") (pinfunction "Q_3") (pintype "output"))
    )
    (net (code "53") (name "Net-(IC9-R)") (class "Default")
      (node (ref "AM2") (pin "1") (pinfunction "1_1") (pintype "passive"))
      (node (ref "IC9") (pin "4") (pinfunction "R_4") (pintype "input"))
      (node (ref "IC9") (pin "8") (pinfunction "V+_8") (pintype "power_in"))
      (node (ref "R3") (pin "1") (pinfunction "1_1") (pintype "passive"))
    )
    (net (code "54") (name "Net-(IC9-THR)") (class "Default")
      (node (ref "IC9") (pin "2") (pinfunction "TR_2") (pintype "input"))
      (node (ref "IC9") (pin "6") (pinfunction "THR_6") (pintype "input"))
      (node (ref "R3") (pin "2") (pinfunction "2_2") (pintype "passive"))
      (node (ref "R4") (pin "1") (pinfunction "1_1") (pintype "passive"))
    )
    (net (code "55") (name "Net-(JP2-Pad2)") (class "Default")
      (node (ref "JP2") (pin "2") (pinfunction "2_2") (pintype "passive"))
      (node (ref "JP3") (pin "1") (pinfunction "1_1") (pintype "passive"))
    )
    (net (code "56") (name "Net-(JP2-Pad3)") (class "Default")
      (node (ref "JP2") (pin "3") (pinfunction "3_3") (pintype "passive"))
      (node (ref "JP4") (pin "2") (pinfunction "2_2") (pintype "passive"))
    )
    (net (code "57") (name "Net-(K1A-P)") (class "Default")
      (node (ref "JP2") (pin "1") (pinfunction "1_1") (pintype "passive"))
      (node (ref "K1") (pin "4") (pinfunction "P_4") (pintype "passive"))
    )
    (net (code "58") (name "Net-(K1A-S)") (class "Default")
      (node (ref "JP3") (pin "2") (pinfunction "2_2") (pintype "passive"))
      (node (ref "K1") (pin "5") (pinfunction "S_5") (pintype "passive"))
    )
    (net (code "59") (name "Net-(K1B-P)") (class "Default")
      (node (ref "JP2") (pin "4") (pinfunction "4_4") (pintype "passive"))
      (node (ref "K1") (pin "9") (pinfunction "P_9") (pintype "passive"))
    )
    (net (code "60") (name "Net-(K1B-S)") (class "Default")
      (node (ref "JP4") (pin "1") (pinfunction "1_1") (pintype "passive"))
      (node (ref "K1") (pin "8") (pinfunction "S_8") (pintype "passive"))
    )
    (net (code "61") (name "Net-(K1C-+)") (class "Default")
      (node (ref "D2") (pin "A") (pinfunction "A_A") (pintype "passive"))
      (node (ref "K1") (pin "1") (pinfunction "+_1") (pintype "passive"))
      (node (ref "T1") (pin "1") (pinfunction "C_1") (pintype "passive"))
    )
    (net (code "62") (name "Net-(K3A-PA)") (class "Default")
      (node (ref "K3") (pin "11@1") (pinfunction "PA_11@1") (pintype "passive"))
      (node (ref "NETZ-AUSGANG") (pin "2") (pinfunction "2_2") (pintype "passive"))
      (node (ref "NETZSCHALTER") (pin "2") (pinfunction "S_2") (pintype "passive"))
    )
    (net (code "63") (name "Net-(K3A-SA)") (class "Default")
      (node (ref "K3") (pin "14@1") (pinfunction "SA_14@1") (pintype "passive"))
      (node (ref "NETZ-EINGANG") (pin "2") (pinfunction "2_2") (pintype "passive"))
      (node (ref "NETZSCHALTER") (pin "1") (pinfunction "P_1") (pintype "passive"))
    )
    (net (code "64") (name "Net-(K3B-2)") (class "Default")
      (node (ref "D3") (pin "A") (pinfunction "A_A") (pintype "passive"))
      (node (ref "K3") (pin "A2") (pinfunction "2_A2") (pintype "passive"))
      (node (ref "T3") (pin "1") (pinfunction "C_1") (pintype "passive"))
    )
    (net (code "65") (name "Net-(MODUL1-A0)") (class "Default")
      (node (ref "MODUL1") (pin "J2.12") (pinfunction "A0_J2.12") (pintype "bidirectional"))
      (node (ref "R20") (pin "1") (pinfunction "1_1") (pintype "passive"))
      (node (ref "RASPI") (pin "3") (pinfunction "3_3") (pintype "passive"))
    )
    (net (code "66") (name "Net-(MODUL1-A1)") (class "Default")
      (node (ref "D4") (pin "C") (pinfunction "C_C") (pintype "passive"))
      (node (ref "MODUL1") (pin "J2.11") (pinfunction "A1_J2.11") (pintype "bidirectional"))
    )
    (net (code "67") (name "Net-(MODUL1-A2)") (class "Default")
      (node (ref "MODUL1") (pin "J2.10") (pinfunction "A2_J2.10") (pintype "bidirectional"))
      (node (ref "R8") (pin "1") (pinfunction "1_1") (pintype "passive"))
    )
    (net (code "68") (name "Net-(MODUL1-A3)") (class "Default")
      (node (ref "MODUL1") (pin "J2.9") (pinfunction "A3_J2.9") (pintype "bidirectional"))
      (node (ref "SYSTEM.ON") (pin "1") (pinfunction "1_1") (pintype "passive"))
    )
    (net (code "69") (name "Net-(MODUL1-D2)") (class "Default")
      (node (ref "MODUL1") (pin "J1.5") (pinfunction "D2_J1.5") (pintype "bidirectional"))
      (node (ref "R9") (pin "1") (pinfunction "1_1") (pintype "passive"))
    )
    (net (code "70") (name "Net-(MODUL1-D10)") (class "Default")
      (node (ref "MODUL1") (pin "J1.13") (pinfunction "D10_J1.13") (pintype "bidirectional"))
      (node (ref "R19") (pin "1") (pinfunction "1_1") (pintype "passive"))
    )
    (net (code "71") (name "Net-(MODUL1-D11{slash}MOSI)") (class "Default")
      (node (ref "MODUL1") (pin "J1.14") (pinfunction "D11/MOSI_J1.14") (pintype "bidirectional"))
      (node (ref "WS2801") (pin "1") (pinfunction "1_1") (pintype "passive"))
    )
    (net (code "72") (name "Net-(MODUL1-D13{slash}SCK)") (class "Default")
      (node (ref "MODUL1") (pin "J2.15") (pinfunction "D13/SCK_J2.15") (pintype "bidirectional"))
      (node (ref "WS2801") (pin "2") (pinfunction "2_2") (pintype "passive"))
    )
    (net (code "73") (name "Net-(NETZ-AUSGANG-Pad1)") (class "Default")
      (node (ref "NETZ-AUSGANG") (pin "1") (pinfunction "1_1") (pintype "passive"))
      (node (ref "NETZ-EINGANG") (pin "1") (pinfunction "1_1") (pintype "passive"))
    )
    (net (code "74") (name "Net-(RASPI_OUT-Pad1)") (class "Default")
      (node (ref "RASPI_OUT") (pin "1") (pinfunction "1_1") (pintype "passive"))
      (node (ref "RE1") (pin "O") (pinfunction "O_O") (pintype "passive"))
    )
    (net (code "75") (name "Net-(RASPI_OUT-Pad3)") (class "Default")
      (node (ref "RASPI_OUT") (pin "3") (pinfunction "3_3") (pintype "passive"))
      (node (ref "RE2") (pin "O") (pinfunction "O_O") (pintype "passive"))
    )
    (net (code "76") (name "Net-(S1-P)") (class "Default")
      (node (ref "S1") (pin "1") (pinfunction "P_1") (pintype "passive"))
      (node (ref "SYS-ON") (pin "1") (pinfunction "1_1") (pintype "passive"))
    )
    (net (code "77") (name "Net-(S1-S)") (class "Default")
      (node (ref "S1") (pin "2") (pinfunction "S_2") (pintype "passive"))
      (node (ref "SYS-ON") (pin "2") (pinfunction "2_2") (pintype "passive"))
    )
    (net (code "78") (name "Net-(T1-B)") (class "Default")
      (node (ref "R8") (pin "2") (pinfunction "2_2") (pintype "passive"))
      (node (ref "T1") (pin "2") (pinfunction "B_2") (pintype "passive"))
    )
    (net (code "79") (name "Net-(T2-B)") (class "Default")
      (node (ref "R9") (pin "2") (pinfunction "2_2") (pintype "passive"))
      (node (ref "T2") (pin "2") (pinfunction "B_2") (pintype "passive"))
    )
    (net (code "80") (name "Net-(T2-C)") (class "Default")
      (node (ref "D1") (pin "A") (pinfunction "A_A") (pintype "passive"))
      (node (ref "RE1") (pin "2") (pinfunction "2_2") (pintype "passive"))
      (node (ref "RE2") (pin "2") (pinfunction "2_2") (pintype "passive"))
      (node (ref "T2") (pin "1") (pinfunction "C_1") (pintype "passive"))
    )
    (net (code "81") (name "Net-(T3-B)") (class "Default")
      (node (ref "R19") (pin "2") (pinfunction "2_2") (pintype "passive"))
      (node (ref "T3") (pin "2") (pinfunction "B_2") (pintype "passive"))
    )
    (net (code "82") (name "Net-(TM1-E)") (class "Default")
      (node (ref "R5") (pin "1") (pinfunction "1_1") (pintype "passive"))
      (node (ref "R6") (pin "1") (pinfunction "1_1") (pintype "passive"))
      (node (ref "TM1") (pin "3") (pinfunction "E_3") (pintype "passive"))
    )
    (net (code "83") (name "Net-(TM1-S)") (class "Default")
      (node (ref "C7") (pin "2") (pinfunction "2_2") (pintype "passive"))
      (node (ref "TM1") (pin "2") (pinfunction "S_2") (pintype "passive"))
    )
    (net (code "84") (name "VCC") (class "Default")
      (node (ref "R10") (pin "1") (pinfunction "1_1") (pintype "passive"))
      (node (ref "R11") (pin "1") (pinfunction "1_1") (pintype "passive"))
      (node (ref "R12") (pin "1") (pinfunction "1_1") (pintype "passive"))
      (node (ref "R13") (pin "1") (pinfunction "1_1") (pintype "passive"))
      (node (ref "R14") (pin "1") (pinfunction "1_1") (pintype "passive"))
      (node (ref "R15") (pin "1") (pinfunction "1_1") (pintype "passive"))
      (node (ref "R16") (pin "1") (pinfunction "1_1") (pintype "passive"))
      (node (ref "R17") (pin "1") (pinfunction "1_1") (pintype "passive"))
      (node (ref "R18") (pin "2") (pinfunction "2_2") (pintype "passive"))
      (node (ref "TASTEN_KB_SEITE") (pin "4") (pinfunction "4_4") (pintype "passive"))
    )
    (net (code "85") (name "unconnected-(IC4-NC1-PadP$3)") (class "Default")
      (node (ref "IC4") (pin "P$3") (pinfunction "NC1_P$3") (pintype "no_connect"))
    )
    (net (code "86") (name "unconnected-(IC4-NC2-PadP$4)") (class "Default")
      (node (ref "IC4") (pin "P$4") (pinfunction "NC2_P$4") (pintype "no_connect"))
    )
    (net (code "87") (name "unconnected-(IC4-NC3-PadP$9)") (class "Default")
      (node (ref "IC4") (pin "P$9") (pinfunction "NC3_P$9") (pintype "no_connect"))
    )
    (net (code "88") (name "unconnected-(IC5A-~{QH}-Pad7)") (class "Default")
      (node (ref "IC5") (pin "7") (pinfunction "~{QH}_7") (pintype "output"))
    )
    (net (code "89") (name "unconnected-(IC6A-~{QH}-Pad7)") (class "Default")
      (node (ref "IC6") (pin "7") (pinfunction "~{QH}_7") (pintype "output"))
    )
    (net (code "90") (name "unconnected-(K1A-O-Pad3)") (class "Default")
      (node (ref "K1") (pin "3") (pinfunction "O_3") (pintype "passive"))
    )
    (net (code "91") (name "unconnected-(K1B-O-Pad10)") (class "Default")
      (node (ref "K1") (pin "10") (pinfunction "O_10") (pintype "passive"))
    )
    (net (code "92") (name "unconnected-(K3A-PB-Pad11@2)") (class "Default")
      (node (ref "K3") (pin "11@2") (pinfunction "PB_11@2") (pintype "passive"))
    )
    (net (code "93") (name "unconnected-(K3A-SB-Pad14@2)") (class "Default")
      (node (ref "K3") (pin "14@2") (pinfunction "SB_14@2") (pintype "passive"))
    )
    (net (code "94") (name "unconnected-(MODUL1-A6-PadJ2.6)") (class "Default")
      (node (ref "MODUL1") (pin "J2.6") (pinfunction "A6_J2.6") (pintype "bidirectional"))
    )
    (net (code "95") (name "unconnected-(MODUL1-D0{slash}RX-PadJ1.2)") (class "Default")
      (node (ref "MODUL1") (pin "J1.2") (pinfunction "D0/RX_J1.2") (pintype "bidirectional"))
    )
    (net (code "96") (name "unconnected-(MODUL1-D1{slash}TX-PadJ1.1)") (class "Default")
      (node (ref "MODUL1") (pin "J1.1") (pinfunction "D1/TX_J1.1") (pintype "bidirectional"))
    )
    (net (code "97") (name "unconnected-(MODUL1-D12{slash}MISO-PadJ1.15)") (class "Default")
      (node (ref "MODUL1") (pin "J1.15") (pinfunction "D12/MISO_J1.15") (pintype "bidirectional"))
    )
    (net (code "98") (name "unconnected-(MODUL1-RESET-PadJ1.3)") (class "Default")
      (node (ref "MODUL1") (pin "J1.3") (pinfunction "RESET_J1.3") (pintype "bidirectional"))
    )
    (net (code "99") (name "unconnected-(MODUL1-RESET-PadJ2.3)") (class "Default")
      (node (ref "MODUL1") (pin "J2.3") (pinfunction "RESET_J2.3") (pintype "bidirectional"))
    )
    (net (code "100") (name "unconnected-(RASPI1-Pad1)") (class "Default")
      (node (ref "RASPI1") (pin "1") (pinfunction "1_1") (pintype "passive"))
    )
    (net (code "101") (name "unconnected-(RASPI1-Pad2)") (class "Default")
      (node (ref "RASPI1") (pin "2") (pinfunction "2_2") (pintype "passive"))
    )
    (net (code "102") (name "unconnected-(RASPI1-Pad3)") (class "Default")
      (node (ref "RASPI1") (pin "3") (pinfunction "3_3") (pintype "passive"))
    )
    (net (code "103") (name "unconnected-(WS2801_IN-Pad1)") (class "Default")
      (node (ref "WS2801_IN") (pin "1") (pinfunction "1_1") (pintype "passive"))
    )
    (net (code "104") (name "unconnected-(WS2801_IN-Pad2)") (class "Default")
      (node (ref "WS2801_IN") (pin "2") (pinfunction "2_2") (pintype "passive"))
    )
    (net (code "105") (name "unconnected-(WS2801_IN-Pad3)") (class "Default")
      (node (ref "WS2801_IN") (pin "3") (pinfunction "3_3") (pintype "passive"))
    )
  )
)
